# NodeMCU_IR_V1_0.net
KiCad netlist of a schematic drawn in Altium Designer
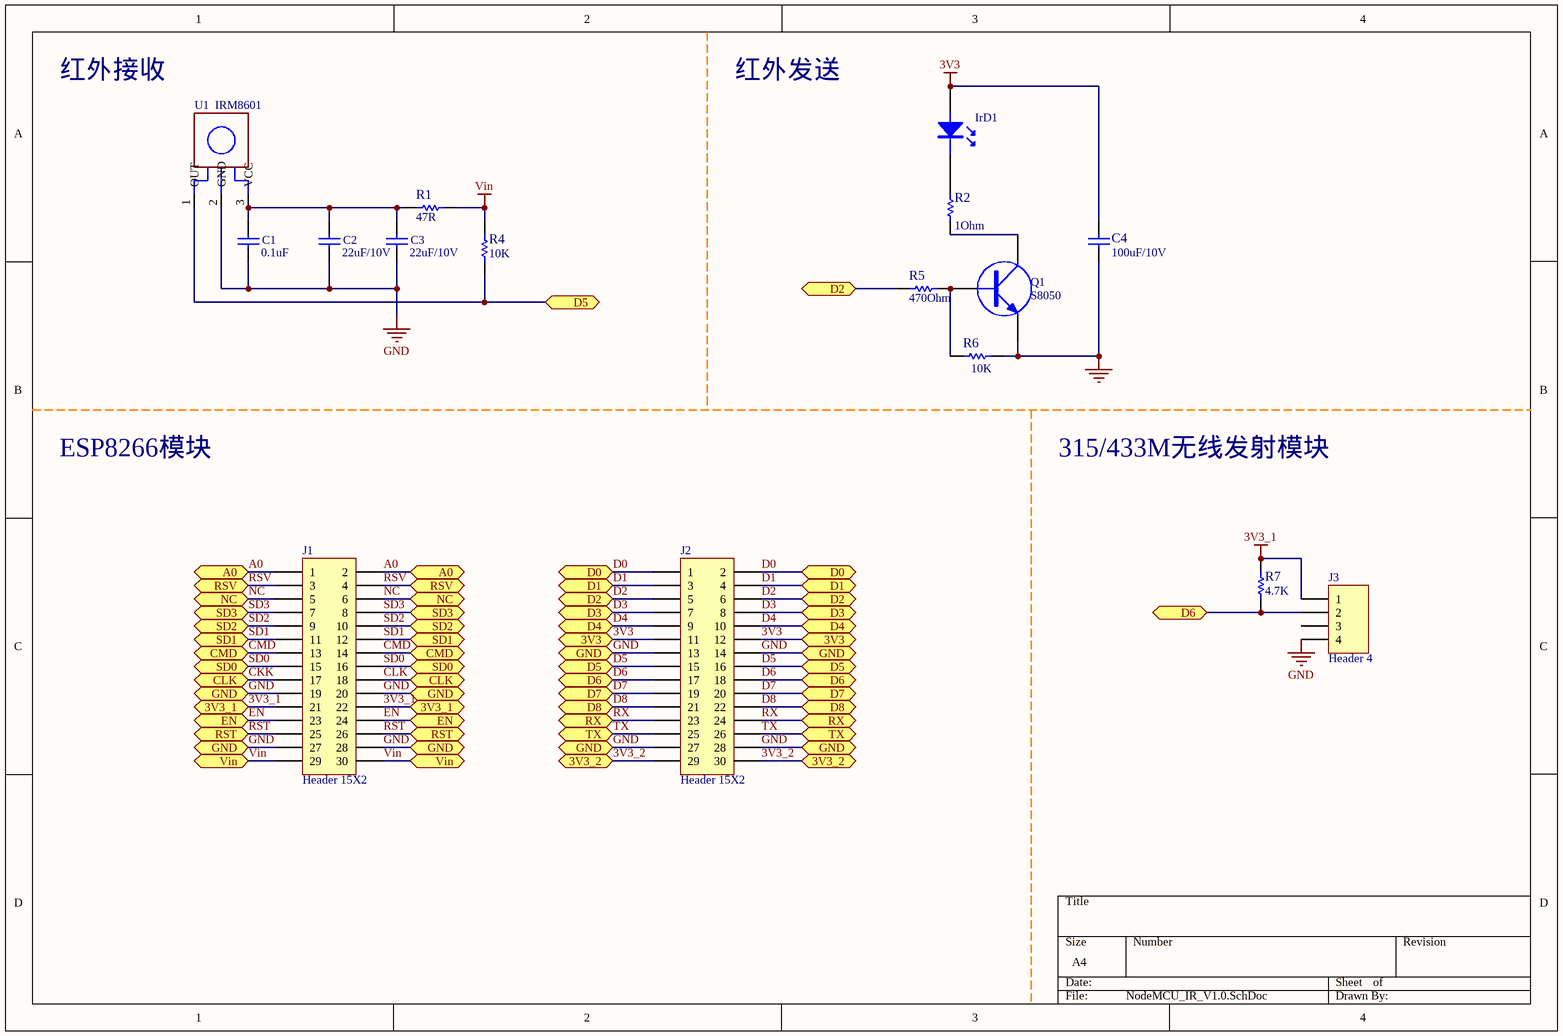
[diagram p0: NodeMCU_IR_V1.0.SchDoc]

(export (version "E")
  (design (tool "Eeschema 10.0.6"))
  (components
    (comp (ref "C1")
      (value "0.1uF")
      (footprint "0805_C")
      (description "Capacitor (Semiconductor SIM Model)")
      (fields (field (name "PUBLISHER") "Altium Limited"))
      (libsource (lib "E606-PCB") (part "Cap Semi"))
    )
    (comp (ref "C2")
      (value "22uF/10V")
      (footprint "1206_C")
      (description "Capacitor (Semiconductor SIM Model)")
      (fields (field (name "PUBLISHER") "Altium Limited"))
      (libsource (lib "E606-PCB") (part "Cap Semi"))
    )
    (comp (ref "C3")
      (value "22uF/10V")
      (footprint "1206_C")
      (description "Capacitor (Semiconductor SIM Model)")
      (fields (field (name "PUBLISHER") "Altium Limited"))
      (libsource (lib "E606-PCB") (part "Cap Semi"))
    )
    (comp (ref "C4")
      (value "100uF/10V")
      (footprint "1206_C")
      (description "ceramic capacitors")
      (fields (field (name "PUBLISHER") "Altium Limited"))
      (libsource (lib "*") (part "ceramic capacitors"))
    )
    (comp (ref "IrD1") (value "~") (footprint "LED-0") (libsource (lib "*") (part "LED")))
    (comp (ref "J1")
      (value "Header 15X2")
      (footprint "HDR2X15")
      (description "Header, 15-Pin, Dual row")
      (fields (field (name "PUBLISHER") "Altium Limited"))
      (libsource (lib "Miscellaneous Connectors") (part "Header 15X2"))
    )
    (comp (ref "J2")
      (value "Header 15X2")
      (footprint "HDR2X15")
      (description "Header, 15-Pin, Dual row")
      (fields (field (name "PUBLISHER") "Altium Limited"))
      (libsource (lib "Miscellaneous Connectors") (part "Header 15X2"))
    )
    (comp (ref "J3")
      (value "Header 4")
      (footprint "DHT11")
      (description "Header, 4-Pin")
      (fields (field (name "PUBLISHER") "Altium Limited"))
      (libsource (lib "Miscellaneous Connectors") (part "Header 4"))
    )
    (comp (ref "Q1")
      (value "S8050")
      (footprint "SOT-SOT23")
      (description "NPN Transistor")
      (libsource (lib "*") (part "NPN"))
    )
    (comp (ref "R1")
      (value "47R")
      (footprint "0805R")
      (description "Resistor")
      (fields (field (name "PUBLISHER") "Altium Limited"))
      (libsource (lib "*") (part "Res1"))
    )
    (comp (ref "R2")
      (value "1Ohm")
      (footprint "0805R")
      (description "Resistor")
      (fields (field (name "PUBLISHER") "Altium Limited"))
      (libsource (lib "") (part "Res1_1"))
    )
    (comp (ref "R4")
      (value "10K")
      (footprint "0805R")
      (description "Resistor")
      (fields (field (name "PUBLISHER") "Altium Limited"))
      (libsource (lib "*") (part "Res1"))
    )
    (comp (ref "R5")
      (value "470Ohm")
      (footprint "0805R")
      (description "Resistor")
      (fields (field (name "PUBLISHER") "Altium Limited"))
      (libsource (lib "*") (part "Res1"))
    )
    (comp (ref "R6")
      (value "10K")
      (footprint "0805R")
      (description "Resistor")
      (fields (field (name "PUBLISHER") "Altium Limited"))
      (libsource (lib "*") (part "Res1"))
    )
    (comp (ref "R7")
      (value "4.7K")
      (footprint "0805R")
      (description "Resistor")
      (fields (field (name "PUBLISHER") "Altium Limited"))
      (libsource (lib "*") (part "Res1"))
    )
    (comp (ref "U1")
      (value "IRM8601")
      (footprint "LED_IR")
      (libsource (lib "Miscellaneous Devices") (part "IR-RCV"))
    )
  )
  (nets
    (net (code "1") (name "/3V3_2") (class "Default")
      (node (ref "J2") (pin "29") (pinfunction "29_29") (pintype "passive"))
      (node (ref "J2") (pin "30") (pinfunction "30_30") (pintype "passive"))
    )
    (net (code "2") (name "/A0") (class "Default")
      (node (ref "J1") (pin "1") (pinfunction "1_1") (pintype "passive"))
      (node (ref "J1") (pin "2") (pinfunction "2_2") (pintype "passive"))
    )
    (net (code "3") (name "/CKK") (class "Default")
      (node (ref "J1") (pin "17") (pinfunction "17_17") (pintype "passive"))
      (node (ref "J1") (pin "18") (pinfunction "18_18") (pintype "passive"))
    )
    (net (code "4") (name "/CMD") (class "Default")
      (node (ref "J1") (pin "13") (pinfunction "13_13") (pintype "passive"))
      (node (ref "J1") (pin "14") (pinfunction "14_14") (pintype "passive"))
    )
    (net (code "5") (name "/D0") (class "Default")
      (node (ref "J2") (pin "1") (pinfunction "1_1") (pintype "passive"))
      (node (ref "J2") (pin "2") (pinfunction "2_2") (pintype "passive"))
    )
    (net (code "6") (name "/D1") (class "Default")
      (node (ref "J2") (pin "3") (pinfunction "3_3") (pintype "passive"))
      (node (ref "J2") (pin "4") (pinfunction "4_4") (pintype "passive"))
    )
    (net (code "7") (name "/D2") (class "Default")
      (node (ref "J2") (pin "5") (pinfunction "5_5") (pintype "passive"))
      (node (ref "J2") (pin "6") (pinfunction "6_6") (pintype "passive"))
      (node (ref "R5") (pin "2") (pinfunction "2_2") (pintype "passive"))
    )
    (net (code "8") (name "/D3") (class "Default")
      (node (ref "J2") (pin "7") (pinfunction "7_7") (pintype "passive"))
      (node (ref "J2") (pin "8") (pinfunction "8_8") (pintype "passive"))
    )
    (net (code "9") (name "/D4") (class "Default")
      (node (ref "J2") (pin "10") (pinfunction "10_10") (pintype "passive"))
      (node (ref "J2") (pin "9") (pinfunction "9_9") (pintype "passive"))
    )
    (net (code "10") (name "/D5") (class "Default")
      (node (ref "J2") (pin "15") (pinfunction "15_15") (pintype "passive"))
      (node (ref "J2") (pin "16") (pinfunction "16_16") (pintype "passive"))
      (node (ref "R4") (pin "2") (pinfunction "2_2") (pintype "passive"))
      (node (ref "U1") (pin "1") (pinfunction "OUT_1") (pintype "passive"))
    )
    (net (code "11") (name "/D6") (class "Default")
      (node (ref "J2") (pin "17") (pinfunction "17_17") (pintype "passive"))
      (node (ref "J2") (pin "18") (pinfunction "18_18") (pintype "passive"))
      (node (ref "J3") (pin "2") (pinfunction "2_2") (pintype "passive"))
      (node (ref "R7") (pin "2") (pinfunction "2_2") (pintype "passive"))
    )
    (net (code "12") (name "/D7") (class "Default")
      (node (ref "J2") (pin "19") (pinfunction "19_19") (pintype "passive"))
      (node (ref "J2") (pin "20") (pinfunction "20_20") (pintype "passive"))
    )
    (net (code "13") (name "/D8") (class "Default")
      (node (ref "J2") (pin "21") (pinfunction "21_21") (pintype "passive"))
      (node (ref "J2") (pin "22") (pinfunction "22_22") (pintype "passive"))
    )
    (net (code "14") (name "/EN") (class "Default")
      (node (ref "J1") (pin "23") (pinfunction "23_23") (pintype "passive"))
      (node (ref "J1") (pin "24") (pinfunction "24_24") (pintype "passive"))
    )
    (net (code "15") (name "/NC") (class "Default")
      (node (ref "J1") (pin "5") (pinfunction "5_5") (pintype "passive"))
      (node (ref "J1") (pin "6") (pinfunction "6_6") (pintype "passive"))
    )
    (net (code "16") (name "/RST") (class "Default")
      (node (ref "J1") (pin "25") (pinfunction "25_25") (pintype "passive"))
      (node (ref "J1") (pin "26") (pinfunction "26_26") (pintype "passive"))
    )
    (net (code "17") (name "/RSV") (class "Default")
      (node (ref "J1") (pin "3") (pinfunction "3_3") (pintype "passive"))
      (node (ref "J1") (pin "4") (pinfunction "4_4") (pintype "passive"))
    )
    (net (code "18") (name "/RX") (class "Default")
      (node (ref "J2") (pin "23") (pinfunction "23_23") (pintype "passive"))
      (node (ref "J2") (pin "24") (pinfunction "24_24") (pintype "passive"))
    )
    (net (code "19") (name "/SD0") (class "Default")
      (node (ref "J1") (pin "15") (pinfunction "15_15") (pintype "passive"))
      (node (ref "J1") (pin "16") (pinfunction "16_16") (pintype "passive"))
    )
    (net (code "20") (name "/SD1") (class "Default")
      (node (ref "J1") (pin "11") (pinfunction "11_11") (pintype "passive"))
      (node (ref "J1") (pin "12") (pinfunction "12_12") (pintype "passive"))
    )
    (net (code "21") (name "/SD2") (class "Default")
      (node (ref "J1") (pin "10") (pinfunction "10_10") (pintype "passive"))
      (node (ref "J1") (pin "9") (pinfunction "9_9") (pintype "passive"))
    )
    (net (code "22") (name "/SD3") (class "Default")
      (node (ref "J1") (pin "7") (pinfunction "7_7") (pintype "passive"))
      (node (ref "J1") (pin "8") (pinfunction "8_8") (pintype "passive"))
    )
    (net (code "23") (name "/TX") (class "Default")
      (node (ref "J2") (pin "25") (pinfunction "25_25") (pintype "passive"))
      (node (ref "J2") (pin "26") (pinfunction "26_26") (pintype "passive"))
    )
    (net (code "24") (name "3V3") (class "Default")
      (node (ref "C4") (pin "1") (pinfunction "1_1") (pintype "passive"))
      (node (ref "IrD1") (pin "A") (pinfunction "1_A") (pintype "passive"))
      (node (ref "J2") (pin "11") (pinfunction "11_11") (pintype "passive"))
      (node (ref "J2") (pin "12") (pinfunction "12_12") (pintype "passive"))
    )
    (net (code "25") (name "3V3_1") (class "Default")
      (node (ref "J1") (pin "21") (pinfunction "21_21") (pintype "passive"))
      (node (ref "J1") (pin "22") (pinfunction "22_22") (pintype "passive"))
      (node (ref "J3") (pin "1") (pinfunction "1_1") (pintype "passive"))
      (node (ref "R7") (pin "1") (pinfunction "1_1") (pintype "passive"))
    )
    (net (code "26") (name "GND") (class "Default")
      (node (ref "C1") (pin "1") (pinfunction "1_1") (pintype "passive"))
      (node (ref "C2") (pin "1") (pinfunction "1_1") (pintype "passive"))
      (node (ref "C3") (pin "1") (pinfunction "1_1") (pintype "passive"))
      (node (ref "C4") (pin "2") (pinfunction "2_2") (pintype "passive"))
      (node (ref "J1") (pin "19") (pinfunction "19_19") (pintype "passive"))
      (node (ref "J1") (pin "20") (pinfunction "20_20") (pintype "passive"))
      (node (ref "J1") (pin "27") (pinfunction "27_27") (pintype "passive"))
      (node (ref "J1") (pin "28") (pinfunction "28_28") (pintype "passive"))
      (node (ref "J2") (pin "13") (pinfunction "13_13") (pintype "passive"))
      (node (ref "J2") (pin "14") (pinfunction "14_14") (pintype "passive"))
      (node (ref "J2") (pin "27") (pinfunction "27_27") (pintype "passive"))
      (node (ref "J2") (pin "28") (pinfunction "28_28") (pintype "passive"))
      (node (ref "J3") (pin "4") (pinfunction "4_4") (pintype "passive"))
      (node (ref "Q1") (pin "E") (pinfunction "E_E") (pintype "passive"))
      (node (ref "R6") (pin "1") (pinfunction "1_1") (pintype "passive"))
      (node (ref "U1") (pin "2") (pinfunction "GND_2") (pintype "passive"))
    )
    (net (code "27") (name "Net-(IrD1-2)") (class "Default")
      (node (ref "IrD1") (pin "K") (pinfunction "2_K") (pintype "passive"))
      (node (ref "R2") (pin "2") (pinfunction "2_2") (pintype "passive"))
    )
    (net (code "28") (name "Net-(Q1-PadB)") (class "Default")
      (node (ref "Q1") (pin "B") (pinfunction "B_B") (pintype "passive"))
      (node (ref "R5") (pin "1") (pinfunction "1_1") (pintype "passive"))
      (node (ref "R6") (pin "2") (pinfunction "2_2") (pintype "passive"))
    )
    (net (code "29") (name "Net-(Q1-PadC)") (class "Default")
      (node (ref "Q1") (pin "C") (pinfunction "C_C") (pintype "passive"))
      (node (ref "R2") (pin "1") (pinfunction "1_1") (pintype "passive"))
    )
    (net (code "30") (name "Net-(U1-VCC)") (class "Default")
      (node (ref "C1") (pin "2") (pinfunction "2_2") (pintype "passive"))
      (node (ref "C2") (pin "2") (pinfunction "2_2") (pintype "passive"))
      (node (ref "C3") (pin "2") (pinfunction "2_2") (pintype "passive"))
      (node (ref "R1") (pin "2") (pinfunction "2_2") (pintype "passive"))
      (node (ref "U1") (pin "3") (pinfunction "VCC_3") (pintype "passive"))
    )
    (net (code "31") (name "Vin") (class "Default")
      (node (ref "J1") (pin "29") (pinfunction "29_29") (pintype "passive"))
      (node (ref "J1") (pin "30") (pinfunction "30_30") (pintype "passive"))
      (node (ref "R1") (pin "1") (pinfunction "1_1") (pintype "passive"))
      (node (ref "R4") (pin "1") (pinfunction "1_1") (pintype "passive"))
    )
    (net (code "32") (name "unconnected-(J3-Pad3)") (class "Default")
      (node (ref "J3") (pin "3") (pinfunction "3_3") (pintype "passive"))
    )
  )
)
